# Armature_Joint_PCB_V1_1.net
KiCad netlist of a schematic drawn in EAGLE
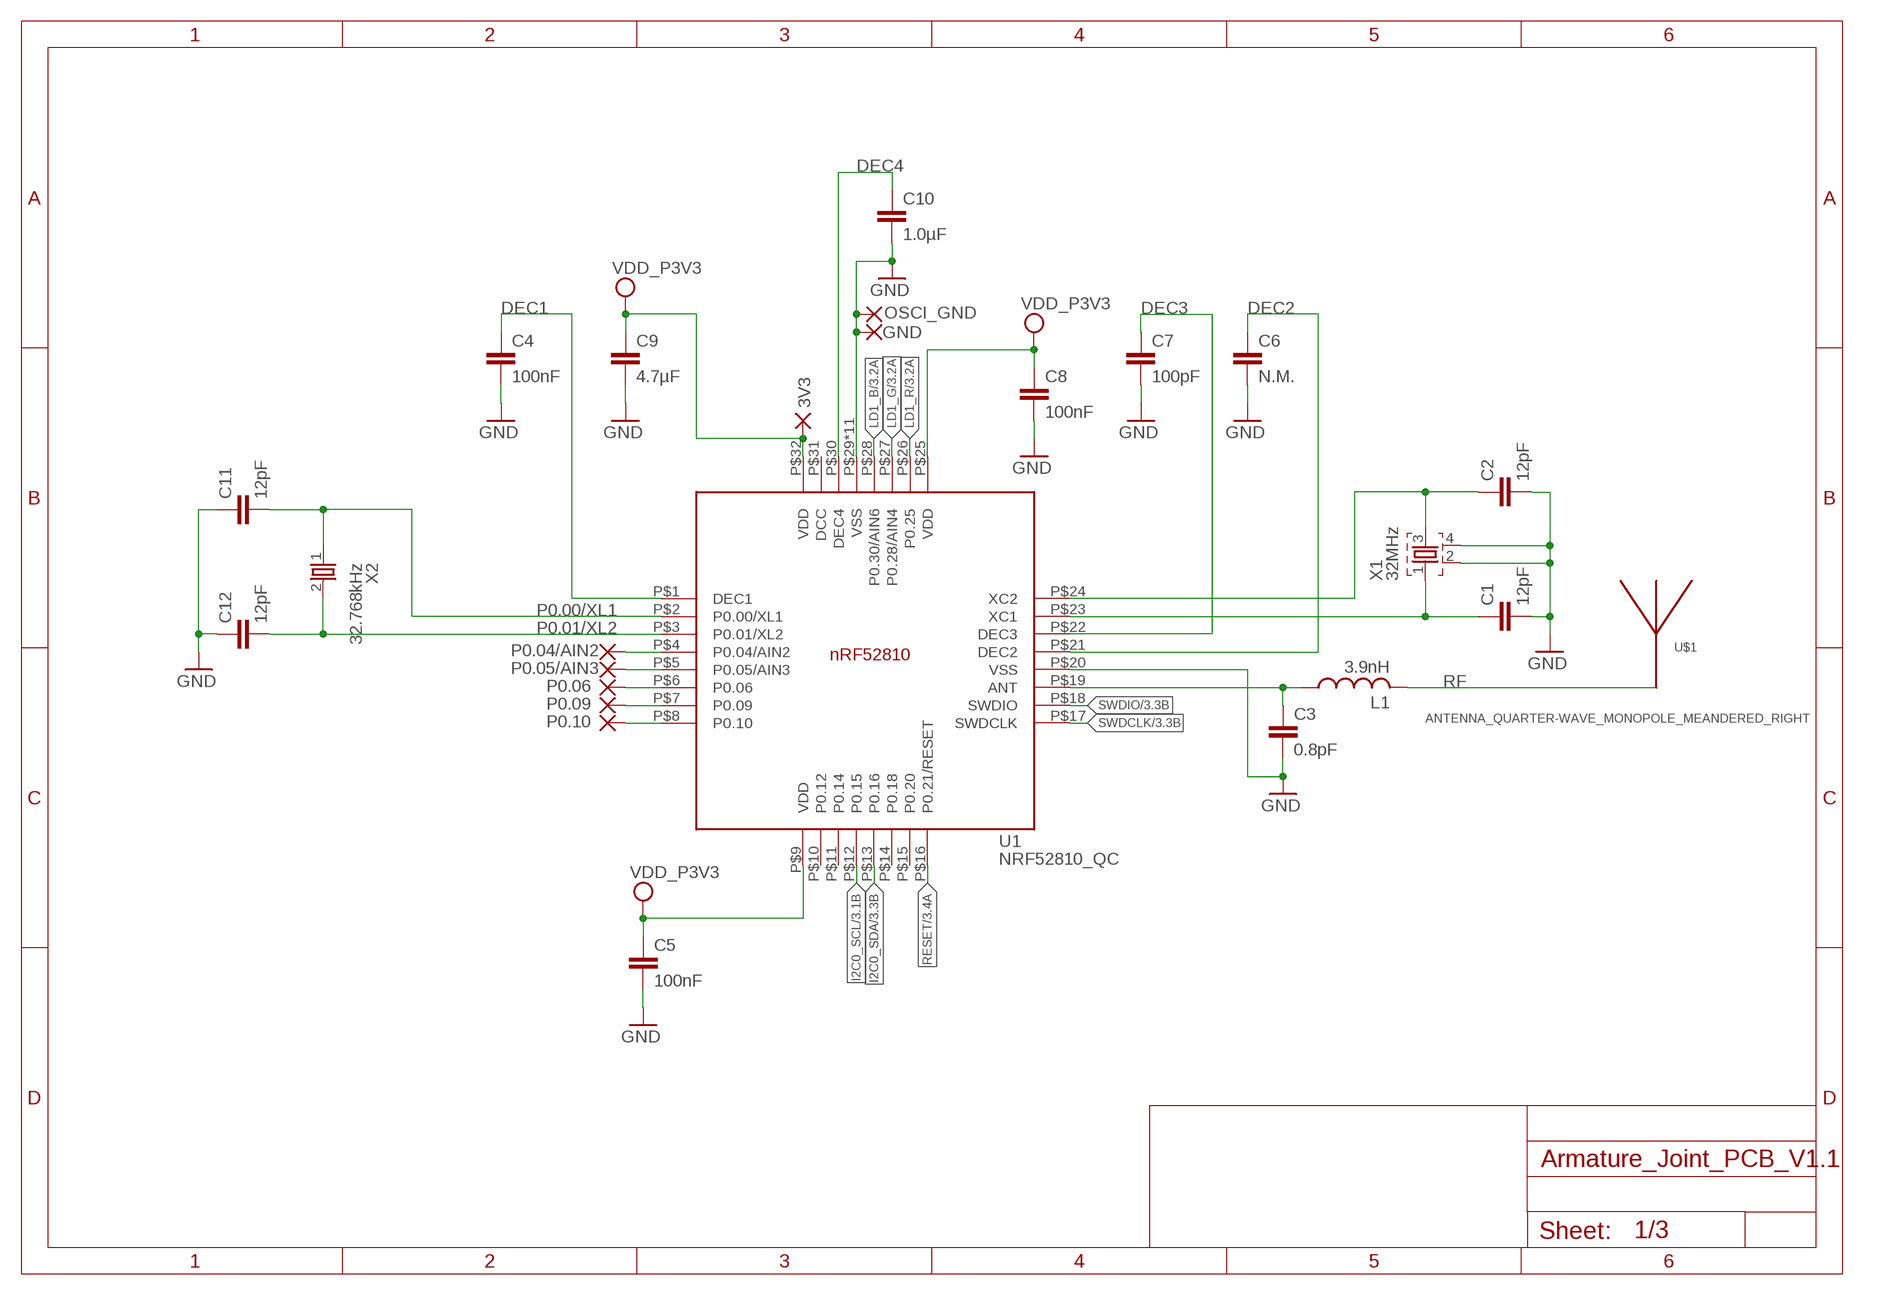
[diagram p0: schematic, sheet 1]
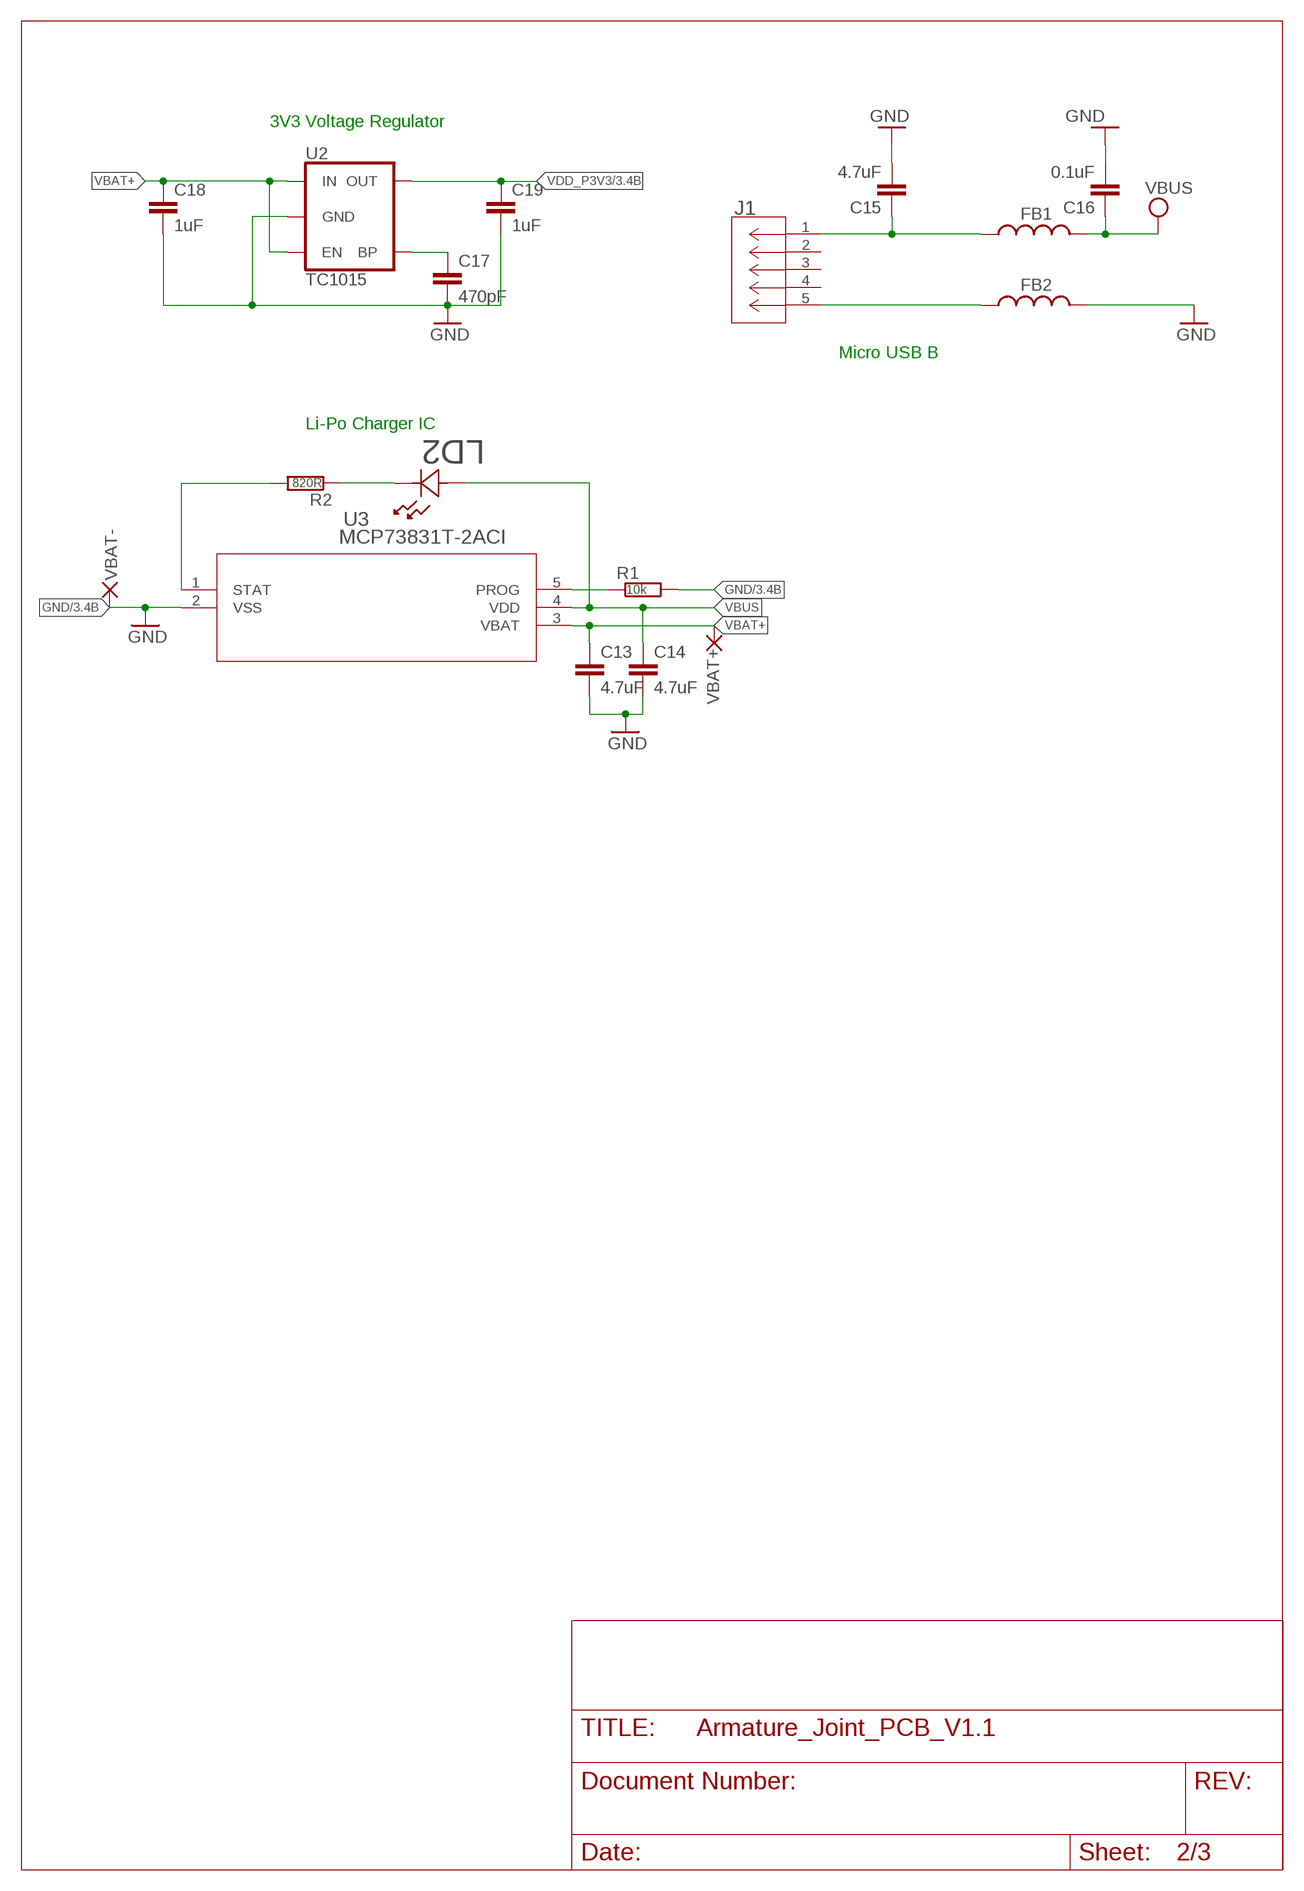
[diagram p1: schematic, sheet 2]
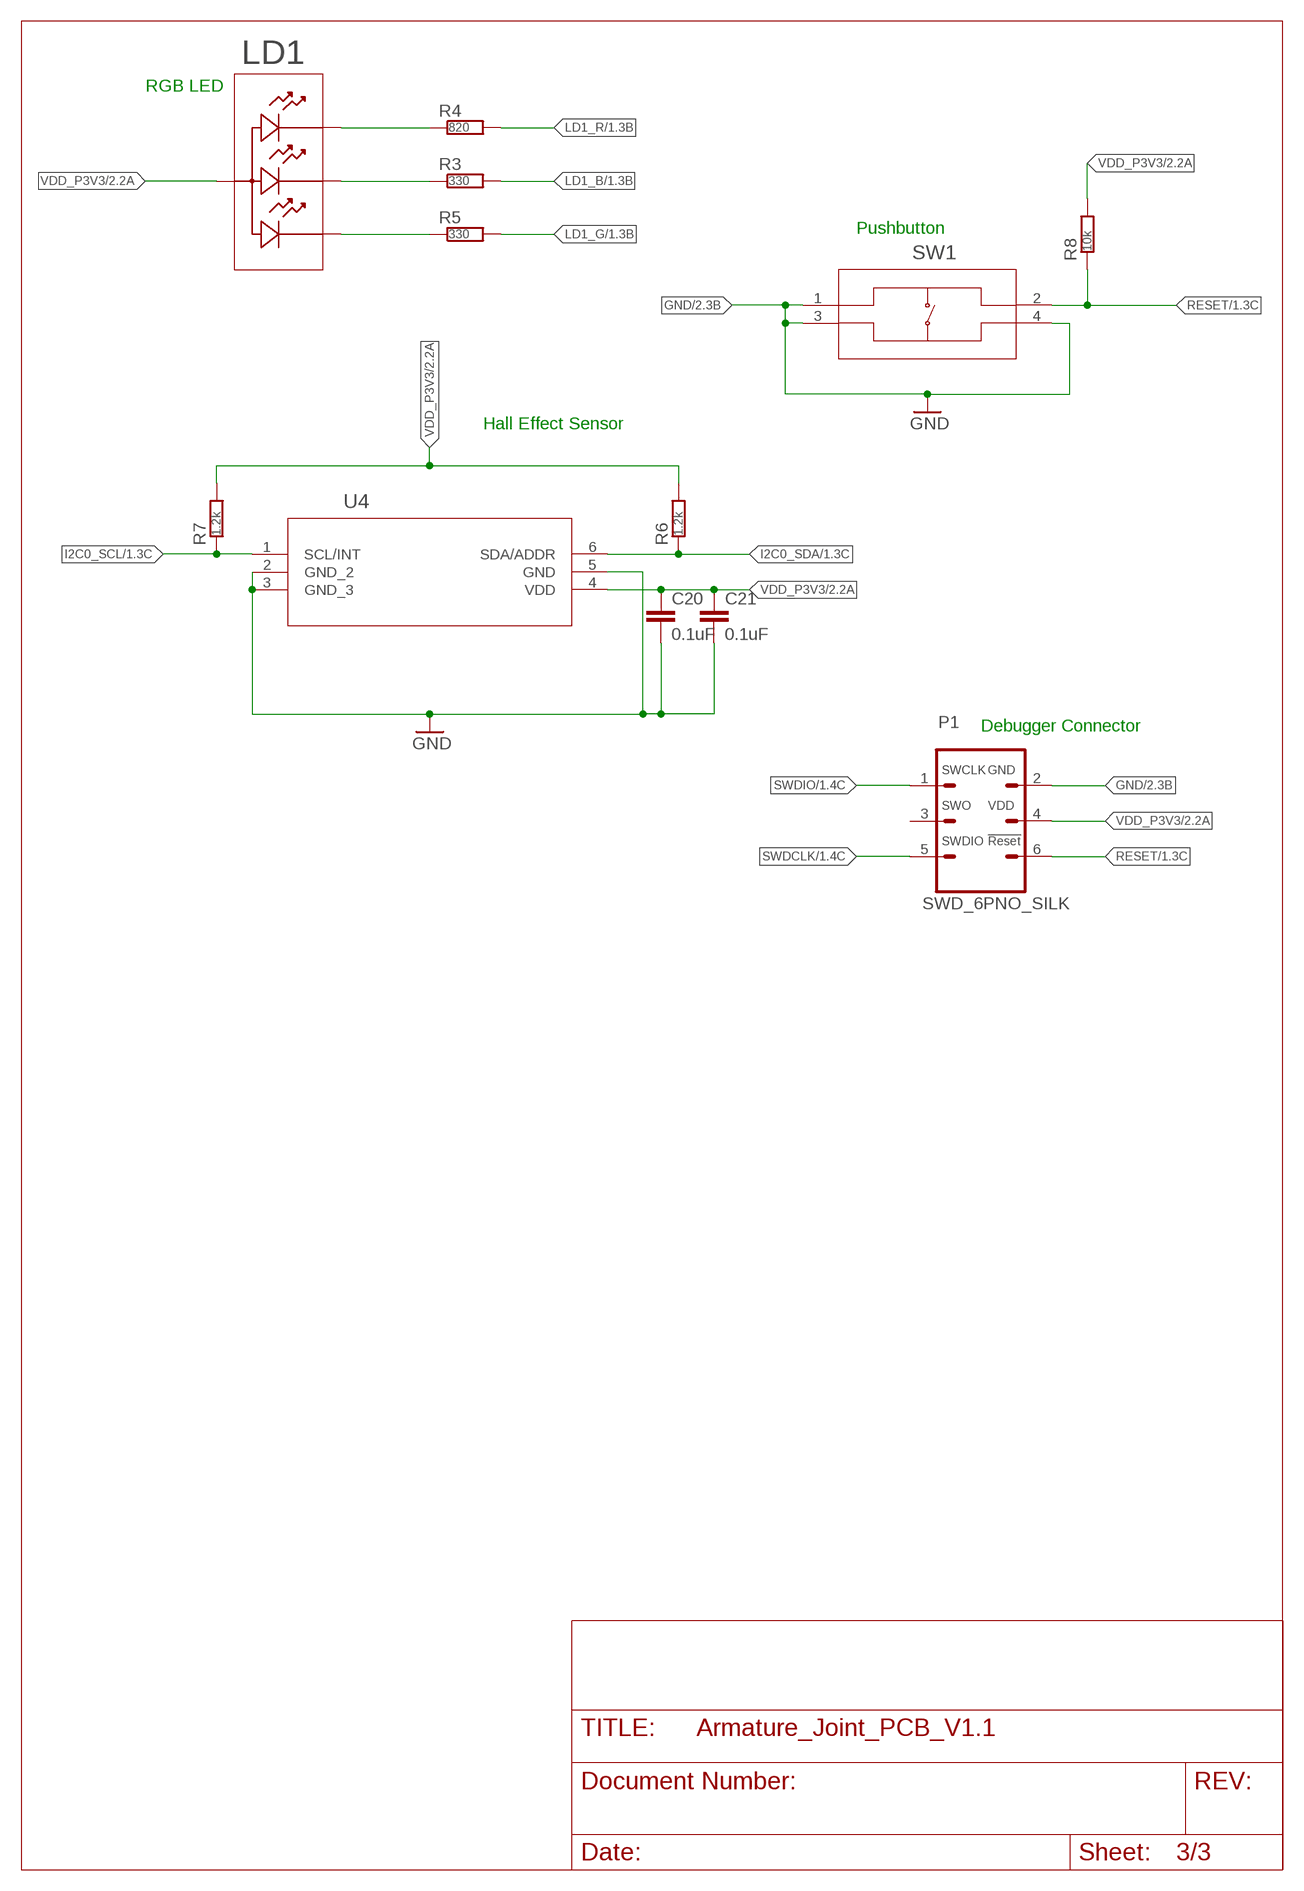
[diagram p2: schematic, sheet 3]

(export (version "E")
  (design (tool "Eeschema 10.0.6"))
  (components
    (comp (ref "C20")
      (value "0.1uF")
      (footprint "eagle-import:RESC0402_M")
      (libsource (lib "eagle-import") (part "CAPACITOR_0402_M"))
    )
    (comp (ref "C21")
      (value "0.1uF")
      (footprint "eagle-import:RESC0402_M")
      (libsource (lib "eagle-import") (part "CAPACITOR_0402_M"))
    )
    (comp (ref "LD1")
      (value "APHF1608SEEQBDZGKCAPHF1608SEEQBDZGKC_KNB-L")
      (footprint "eagle-import:APHF1608SEEQBDZGKC_KNB-L")
      (fields
        (field (name "MANUFACTURER_PART_NUMBER") "APHF1608SEEQBDZGKC")
        (field (name "COPYRIGHT") "Copyright (C) 2018 Accelerated Designs. All rights reserved")
      )
      (libsource (lib "eagle-import") (part "APHF1608SEEQBDZGKCAPHF1608SEEQBDZGKC_KNB-L"))
    )
    (comp (ref "P1")
      (value "SWD_6PNO_SILK")
      (footprint "eagle-import:SWD_6P")
      (libsource (lib "eagle-import") (part "SWD_6PNO_SILK"))
    )
    (comp (ref "R3")
      (value "330")
      (footprint "eagle-import:RESC0402_N")
      (libsource (lib "eagle-import") (part "RESISTOR_0402_N"))
    )
    (comp (ref "R4")
      (value "820")
      (footprint "eagle-import:RESC0402_N")
      (libsource (lib "eagle-import") (part "RESISTOR_0402_N"))
    )
    (comp (ref "R5")
      (value "330")
      (footprint "eagle-import:RESC0402_N")
      (libsource (lib "eagle-import") (part "RESISTOR_0402_N"))
    )
    (comp (ref "R6")
      (value "1.2k")
      (footprint "eagle-import:RESC0402_N")
      (libsource (lib "eagle-import") (part "RESISTOR_0402_N"))
    )
    (comp (ref "R7")
      (value "1.2k")
      (footprint "eagle-import:RESC0402_N")
      (libsource (lib "eagle-import") (part "RESISTOR_0402_N"))
    )
    (comp (ref "R8")
      (value "10k")
      (footprint "eagle-import:RESC0402_N")
      (libsource (lib "eagle-import") (part "RESISTOR_0402_N"))
    )
    (comp (ref "SW1")
      (value "PTS810SJG250SMTRLFS")
      (footprint "eagle-import:PTS810")
      (fields (field (name "COPYRIGHT") "Copyright (C) 2018 Accelerated Designs. All rights reserved"))
      (libsource (lib "eagle-import") (part "PTS810SJG250SMTRLFS"))
    )
    (comp (ref "U4")
      (value "TLV493DA1B6HTSA2")
      (footprint "eagle-import:PG-TSOP6-6-5_INF")
      (fields (field (name "COPYRIGHT") "Copyright (C) 2018 Accelerated Designs. All rights reserved"))
      (libsource (lib "eagle-import") (part "TLV493DA1B6HTSA2"))
    )
    (comp (ref "C13")
      (value "4.7uF")
      (footprint "eagle-import:RESC0603_N")
      (libsource (lib "eagle-import") (part "CAPACITORCAP_0603_N"))
    )
    (comp (ref "C14")
      (value "4.7uF")
      (footprint "eagle-import:RESC0603_N")
      (libsource (lib "eagle-import") (part "CAPACITORCAP_0603_N"))
    )
    (comp (ref "C15")
      (value "4.7uF")
      (footprint "eagle-import:RESC0603_N")
      (libsource (lib "eagle-import") (part "CAPACITORCAP_0603_N"))
    )
    (comp (ref "C16")
      (value "0.1uF")
      (footprint "eagle-import:RESC0603_N")
      (libsource (lib "eagle-import") (part "CAPACITORCAP_0603_N"))
    )
    (comp (ref "C17")
      (value "470pF")
      (footprint "eagle-import:RESC0402_N")
      (libsource (lib "eagle-import") (part "CAPACITOR"))
    )
    (comp (ref "C18")
      (value "1uF")
      (footprint "eagle-import:RESC0603_N")
      (libsource (lib "eagle-import") (part "CAPACITORCAP_0603_N"))
    )
    (comp (ref "C19")
      (value "1uF")
      (footprint "eagle-import:RESC0603_N")
      (libsource (lib "eagle-import") (part "CAPACITORCAP_0603_N"))
    )
    (comp (ref "FB1")
      (value "FERRITE_BEAD")
      (footprint "eagle-import:RESC0402_M")
      (libsource (lib "eagle-import") (part "FERRITE_BEAD"))
    )
    (comp (ref "FB2")
      (value "FERRITE_BEAD")
      (footprint "eagle-import:RESC0402_M")
      (libsource (lib "eagle-import") (part "FERRITE_BEAD"))
    )
    (comp (ref "J1")
      (value "10118192-0002LF")
      (footprint "eagle-import:CONN_10118192-0002LF_AMP")
      (fields (field (name "COPYRIGHT") "Copyright (C) 2018 Accelerated Designs. All rights reserved"))
      (libsource (lib "eagle-import") (part "10118192-0002LF"))
    )
    (comp (ref "LD2")
      (value "LBQH9G-N1OO-35-1")
      (footprint "eagle-import:LED_SML-LX0402SYC-TR_LUM-M")
      (libsource (lib "eagle-import") (part "LBQH9G-N1OO-35-1"))
    )
    (comp (ref "R1")
      (value "10k")
      (footprint "eagle-import:RESC0402_N")
      (libsource (lib "eagle-import") (part "RESISTOR_0402_N"))
    )
    (comp (ref "R2")
      (value "820R")
      (footprint "eagle-import:RESC0402_N")
      (libsource (lib "eagle-import") (part "RESISTOR_0402_N"))
    )
    (comp (ref "U2")
      (value "TC1015")
      (footprint "eagle-import:SOT23-5")
      (libsource (lib "eagle-import") (part "TC1015"))
    )
    (comp (ref "U3")
      (value "MCP73831T-2ACI")
      (footprint "eagle-import:SOT-23-5_MC_MCH")
      (fields (field (name "MANUFACTURER_PART_NUMBER") "MCP73831T-2ACI/OT"))
      (libsource (lib "eagle-import") (part "MCP73831T-2ACI/OT"))
    )
    (comp (ref "VBAT+")
      (value "VBAT+")
      (footprint "eagle-import:SMD1,27-2,54")
      (libsource (lib "eagle-import") (part "SMD2"))
    )
    (comp (ref "VBAT-")
      (value "GND")
      (footprint "eagle-import:SMD1,27-2,54")
      (libsource (lib "eagle-import") (part "SMD2"))
    )
    (comp (ref "3V3")
      (value "vdd_p3v3")
      (footprint "eagle-import:SMD1,27-2,54")
      (libsource (lib "eagle-import") (part "SMD2"))
    )
    (comp (ref "C1")
      (value "12pF")
      (footprint "eagle-import:RESC0402_N")
      (libsource (lib "eagle-import") (part "CAPACITOR"))
    )
    (comp (ref "C2")
      (value "12pF")
      (footprint "eagle-import:RESC0402_N")
      (libsource (lib "eagle-import") (part "CAPACITOR"))
    )
    (comp (ref "C3")
      (value "0.8pF")
      (footprint "eagle-import:RESC0402_N")
      (libsource (lib "eagle-import") (part "CAPACITOR"))
    )
    (comp (ref "C4")
      (value "100nF")
      (footprint "eagle-import:RESC0402_N")
      (libsource (lib "eagle-import") (part "CAPACITOR"))
    )
    (comp (ref "C5")
      (value "100nF")
      (footprint "eagle-import:RESC0402_N")
      (libsource (lib "eagle-import") (part "CAPACITOR"))
    )
    (comp (ref "C6")
      (value "N.M.")
      (footprint "eagle-import:RESC0402_N")
      (libsource (lib "eagle-import") (part "CAPACITOR"))
    )
    (comp (ref "C7")
      (value "100pF")
      (footprint "eagle-import:RESC0402_N")
      (libsource (lib "eagle-import") (part "CAPACITOR"))
    )
    (comp (ref "C8")
      (value "100nF")
      (footprint "eagle-import:RESC0402_N")
      (libsource (lib "eagle-import") (part "CAPACITOR"))
    )
    (comp (ref "C9")
      (value "4.7µF")
      (footprint "eagle-import:RESC0603_N")
      (libsource (lib "eagle-import") (part "CAPACITORCAP_0603_N"))
    )
    (comp (ref "C10")
      (value "1.0µF")
      (footprint "eagle-import:RESC0603_N")
      (libsource (lib "eagle-import") (part "CAPACITORCAP_0603_N"))
    )
    (comp (ref "C11")
      (value "12pF")
      (footprint "eagle-import:RESC0402_N")
      (libsource (lib "eagle-import") (part "CAPACITOR"))
    )
    (comp (ref "C12")
      (value "12pF")
      (footprint "eagle-import:RESC0402_N")
      (libsource (lib "eagle-import") (part "CAPACITOR"))
    )
    (comp (ref "GND")
      (value "GND")
      (footprint "eagle-import:SMD1,27-2,54")
      (libsource (lib "eagle-import") (part "SMD2"))
    )
    (comp (ref "L1")
      (value "3.9nH")
      (footprint "eagle-import:RESC0402_N")
      (libsource (lib "eagle-import") (part "INDUCTOR_0402_N"))
    )
    (comp (ref "OSCI_GND")
      (value "GND")
      (footprint "eagle-import:2,15_1,0")
      (libsource (lib "eagle-import") (part "2,15/1,0"))
    )
    (comp (ref "P0.04/AIN2")
      (value "P0.04/AIN2")
      (footprint "eagle-import:SMD1,27-2,54")
      (libsource (lib "eagle-import") (part "SMD2"))
    )
    (comp (ref "P0.05/AIN3")
      (value "P0.05/AIN3")
      (footprint "eagle-import:SMD1,27-2,54")
      (libsource (lib "eagle-import") (part "SMD2"))
    )
    (comp (ref "P0.06")
      (value "P0.06")
      (footprint "eagle-import:SMD1,27-2,54")
      (libsource (lib "eagle-import") (part "SMD2"))
    )
    (comp (ref "P0.09")
      (value "P0.09")
      (footprint "eagle-import:SMD1,27-2,54")
      (libsource (lib "eagle-import") (part "SMD2"))
    )
    (comp (ref "P0.10")
      (value "P0.10")
      (footprint "eagle-import:SMD1,27-2,54")
      (libsource (lib "eagle-import") (part "SMD2"))
    )
    (comp (ref "U$1")
      (value "ANTENNA_QUARTER-WAVE_MONOPOLE_MEANDERED_RIGHT")
      (footprint "eagle-import:QWMP_MEANDERED_RIGHT_+6")
      (libsource (lib "eagle-import") (part "ANTENNA_QUARTER-WAVE_MONOPOLE_MEANDERED_RIGHT"))
    )
    (comp (ref "U1")
      (value "NRF52810_QC")
      (footprint "eagle-import:QFN50P500X500X90-32_N")
      (libsource (lib "eagle-import") (part "NRF52810_QC"))
    )
    (comp (ref "X1")
      (value "32MHz")
      (footprint "eagle-import:BT-XTAL_2016_N")
      (libsource (lib "eagle-import") (part "XTAL_32MHZ"))
    )
    (comp (ref "X2")
      (value "32.768kHz")
      (footprint "eagle-import:XTAL_3215_N")
      (libsource (lib "eagle-import") (part "XTAL_32KHZ"))
    )
  )
  (nets
    (net (code "1") (name "DEC1") (class "Default")
      (node (ref "C4") (pin "1") (pinfunction "1_1") (pintype "passive"))
      (node (ref "U1") (pin "P$1") (pinfunction "DEC1_P$1") (pintype "bidirectional"))
    )
    (net (code "2") (name "DEC2") (class "Default")
      (node (ref "C6") (pin "1") (pinfunction "1_1") (pintype "passive"))
      (node (ref "U1") (pin "P$21") (pinfunction "DEC2_P$21") (pintype "bidirectional"))
    )
    (net (code "3") (name "DEC3") (class "Default")
      (node (ref "C7") (pin "1") (pinfunction "1_1") (pintype "passive"))
      (node (ref "U1") (pin "P$22") (pinfunction "DEC3_P$22") (pintype "bidirectional"))
    )
    (net (code "4") (name "DEC4") (class "Default")
      (node (ref "C10") (pin "1") (pinfunction "1_1") (pintype "passive"))
      (node (ref "U1") (pin "P$30") (pinfunction "DEC4_P$30") (pintype "bidirectional"))
    )
    (net (code "5") (name "GND") (class "Default")
      (node (ref "C1") (pin "2") (pinfunction "2_2") (pintype "passive"))
      (node (ref "C10") (pin "2") (pinfunction "2_2") (pintype "passive"))
      (node (ref "C11") (pin "1") (pinfunction "1_1") (pintype "passive"))
      (node (ref "C12") (pin "1") (pinfunction "1_1") (pintype "passive"))
      (node (ref "C13") (pin "2") (pinfunction "2_2") (pintype "passive"))
      (node (ref "C14") (pin "2") (pinfunction "2_2") (pintype "passive"))
      (node (ref "C15") (pin "2") (pinfunction "2_2") (pintype "passive"))
      (node (ref "C16") (pin "2") (pinfunction "2_2") (pintype "passive"))
      (node (ref "C17") (pin "2") (pinfunction "2_2") (pintype "passive"))
      (node (ref "C18") (pin "2") (pinfunction "2_2") (pintype "passive"))
      (node (ref "C19") (pin "2") (pinfunction "2_2") (pintype "passive"))
      (node (ref "C2") (pin "2") (pinfunction "2_2") (pintype "passive"))
      (node (ref "C20") (pin "2") (pinfunction "2_2") (pintype "passive"))
      (node (ref "C21") (pin "2") (pinfunction "2_2") (pintype "passive"))
      (node (ref "C3") (pin "2") (pinfunction "2_2") (pintype "passive"))
      (node (ref "C4") (pin "2") (pinfunction "2_2") (pintype "passive"))
      (node (ref "C5") (pin "2") (pinfunction "2_2") (pintype "passive"))
      (node (ref "C6") (pin "2") (pinfunction "2_2") (pintype "passive"))
      (node (ref "C7") (pin "2") (pinfunction "2_2") (pintype "passive"))
      (node (ref "C8") (pin "2") (pinfunction "2_2") (pintype "passive"))
      (node (ref "C9") (pin "2") (pinfunction "2_2") (pintype "passive"))
      (node (ref "FB2") (pin "2") (pinfunction "2_2") (pintype "passive"))
      (node (ref "GND") (pin "1") (pinfunction "P_1") (pintype "passive"))
      (node (ref "OSCI_GND") (pin "1") (pinfunction "P_1") (pintype "passive"))
      (node (ref "P1") (pin "2") (pinfunction "2_2") (pintype "bidirectional"))
      (node (ref "R1") (pin "2") (pinfunction "2_2") (pintype "passive"))
      (node (ref "SW1") (pin "1") (pinfunction "1_1") (pintype "passive"))
      (node (ref "SW1") (pin "3") (pinfunction "3_3") (pintype "passive"))
      (node (ref "SW1") (pin "4") (pinfunction "4_4") (pintype "passive"))
      (node (ref "U1") (pin "P$20") (pinfunction "VSS_P$20") (pintype "bidirectional"))
      (node (ref "U1") (pin "P$29") (pinfunction "VSS_P$29") (pintype "bidirectional"))
      (node (ref "U1") (pin "P$33") (pinfunction "VSS_P$33") (pintype "bidirectional"))
      (node (ref "U1") (pin "P$34") (pinfunction "VSS_P$34") (pintype "bidirectional"))
      (node (ref "U1") (pin "P$35") (pinfunction "VSS_P$35") (pintype "bidirectional"))
      (node (ref "U1") (pin "P$36") (pinfunction "VSS_P$36") (pintype "bidirectional"))
      (node (ref "U1") (pin "P$37") (pinfunction "VSS_P$37") (pintype "bidirectional"))
      (node (ref "U1") (pin "P$38") (pinfunction "VSS_P$38") (pintype "bidirectional"))
      (node (ref "U1") (pin "P$39") (pinfunction "VSS_P$39") (pintype "bidirectional"))
      (node (ref "U1") (pin "P$40") (pinfunction "VSS_P$40") (pintype "bidirectional"))
      (node (ref "U1") (pin "P$41") (pinfunction "VSS_P$41") (pintype "bidirectional"))
      (node (ref "U1") (pin "P$42") (pinfunction "VSS_P$42") (pintype "bidirectional"))
      (node (ref "U2") (pin "2") (pinfunction "GND_2") (pintype "input"))
      (node (ref "U3") (pin "2") (pinfunction "VSS_2") (pintype "passive"))
      (node (ref "U4") (pin "2") (pinfunction "GND_2_2") (pintype "passive"))
      (node (ref "U4") (pin "3") (pinfunction "GND_3_3") (pintype "passive"))
      (node (ref "U4") (pin "5") (pinfunction "GND_5") (pintype "passive"))
      (node (ref "VBAT-") (pin "1") (pinfunction "P_1") (pintype "passive"))
      (node (ref "X1") (pin "2") (pinfunction "2_2") (pintype "passive"))
      (node (ref "X1") (pin "4") (pinfunction "4_4") (pintype "passive"))
    )
    (net (code "6") (name "I2C0_SCL") (class "Default")
      (node (ref "R7") (pin "1") (pinfunction "1_1") (pintype "passive"))
      (node (ref "U1") (pin "P$12") (pinfunction "P0.15_P$12") (pintype "bidirectional"))
      (node (ref "U4") (pin "1") (pinfunction "SCL/INT_1") (pintype "input"))
    )
    (net (code "7") (name "I2C0_SDA") (class "Default")
      (node (ref "R6") (pin "1") (pinfunction "1_1") (pintype "passive"))
      (node (ref "U1") (pin "P$13") (pinfunction "P0.16_P$13") (pintype "bidirectional"))
      (node (ref "U4") (pin "6") (pinfunction "SDA/ADDR_6") (pintype "bidirectional"))
    )
    (net (code "8") (name "LD1_B") (class "Default")
      (node (ref "R3") (pin "2") (pinfunction "2_2") (pintype "passive"))
      (node (ref "U1") (pin "P$28") (pinfunction "P0.30/AIN6_P$28") (pintype "bidirectional"))
    )
    (net (code "9") (name "LD1_G") (class "Default")
      (node (ref "R5") (pin "2") (pinfunction "2_2") (pintype "passive"))
      (node (ref "U1") (pin "P$27") (pinfunction "P0.28/AIN4_P$27") (pintype "bidirectional"))
    )
    (net (code "10") (name "LD1_R") (class "Default")
      (node (ref "R4") (pin "2") (pinfunction "2_2") (pintype "passive"))
      (node (ref "U1") (pin "P$26") (pinfunction "P0.25_P$26") (pintype "bidirectional"))
    )
    (net (code "11") (name "Net-(C15-Pad1)") (class "Default")
      (node (ref "C15") (pin "1") (pinfunction "1_1") (pintype "passive"))
      (node (ref "FB1") (pin "1") (pinfunction "1_1") (pintype "passive"))
      (node (ref "J1") (pin "1") (pinfunction "1_1") (pintype "passive"))
    )
    (net (code "12") (name "Net-(FB2-Pad1)") (class "Default")
      (node (ref "FB2") (pin "1") (pinfunction "1_1") (pintype "passive"))
      (node (ref "J1") (pin "5") (pinfunction "5_5") (pintype "passive"))
    )
    (net (code "13") (name "Net-(LD1-Pad2)") (class "Default")
      (node (ref "LD1") (pin "2") (pinfunction "2_2") (pintype "passive"))
      (node (ref "R4") (pin "1") (pinfunction "1_1") (pintype "passive"))
    )
    (net (code "14") (name "Net-(LD1-Pad3)") (class "Default")
      (node (ref "LD1") (pin "3") (pinfunction "3_3") (pintype "passive"))
      (node (ref "R3") (pin "1") (pinfunction "1_1") (pintype "passive"))
    )
    (net (code "15") (name "Net-(LD1-Pad4)") (class "Default")
      (node (ref "LD1") (pin "4") (pinfunction "4_4") (pintype "passive"))
      (node (ref "R5") (pin "1") (pinfunction "1_1") (pintype "passive"))
    )
    (net (code "16") (name "Net-(LD2-Pad1)") (class "Default")
      (node (ref "LD2") (pin "1") (pinfunction "1_1") (pintype "passive"))
      (node (ref "R2") (pin "1") (pinfunction "1_1") (pintype "passive"))
    )
    (net (code "17") (name "Net-(P0.04/AIN2-P)") (class "Default")
      (node (ref "P0.04/AIN2") (pin "1") (pinfunction "P_1") (pintype "passive"))
      (node (ref "U1") (pin "P$4") (pinfunction "P0.04/AIN2_P$4") (pintype "bidirectional"))
    )
    (net (code "18") (name "Net-(P0.05/AIN3-P)") (class "Default")
      (node (ref "P0.05/AIN3") (pin "1") (pinfunction "P_1") (pintype "passive"))
      (node (ref "U1") (pin "P$5") (pinfunction "P0.05/AIN3_P$5") (pintype "bidirectional"))
    )
    (net (code "19") (name "Net-(P0.06-P)") (class "Default")
      (node (ref "P0.06") (pin "1") (pinfunction "P_1") (pintype "passive"))
      (node (ref "U1") (pin "P$6") (pinfunction "P0.06_P$6") (pintype "bidirectional"))
    )
    (net (code "20") (name "Net-(P0.09-P)") (class "Default")
      (node (ref "P0.09") (pin "1") (pinfunction "P_1") (pintype "passive"))
      (node (ref "U1") (pin "P$7") (pinfunction "P0.09_P$7") (pintype "bidirectional"))
    )
    (net (code "21") (name "Net-(P0.10-P)") (class "Default")
      (node (ref "P0.10") (pin "1") (pinfunction "P_1") (pintype "passive"))
      (node (ref "U1") (pin "P$8") (pinfunction "P0.10_P$8") (pintype "bidirectional"))
    )
    (net (code "22") (name "Net-(U1-ANT)") (class "Default")
      (node (ref "C3") (pin "1") (pinfunction "1_1") (pintype "passive"))
      (node (ref "L1") (pin "1") (pinfunction "1_1") (pintype "passive"))
      (node (ref "U1") (pin "P$19") (pinfunction "ANT_P$19") (pintype "bidirectional"))
    )
    (net (code "23") (name "Net-(U1-XC1)") (class "Default")
      (node (ref "C1") (pin "1") (pinfunction "1_1") (pintype "passive"))
      (node (ref "U1") (pin "P$23") (pinfunction "XC1_P$23") (pintype "bidirectional"))
      (node (ref "X1") (pin "1") (pinfunction "1_1") (pintype "passive"))
    )
    (net (code "24") (name "Net-(U1-XC2)") (class "Default")
      (node (ref "C2") (pin "1") (pinfunction "1_1") (pintype "passive"))
      (node (ref "U1") (pin "P$24") (pinfunction "XC2_P$24") (pintype "bidirectional"))
      (node (ref "X1") (pin "3") (pinfunction "3_3") (pintype "passive"))
    )
    (net (code "25") (name "Net-(U2-BP)") (class "Default")
      (node (ref "C17") (pin "1") (pinfunction "1_1") (pintype "passive"))
      (node (ref "U2") (pin "4") (pinfunction "BP_4") (pintype "input"))
    )
    (net (code "26") (name "Net-(U3-PROG)") (class "Default")
      (node (ref "R1") (pin "1") (pinfunction "1_1") (pintype "passive"))
      (node (ref "U3") (pin "5") (pinfunction "PROG_5") (pintype "passive"))
    )
    (net (code "27") (name "Net-(U3-STAT)") (class "Default")
      (node (ref "R2") (pin "2") (pinfunction "2_2") (pintype "passive"))
      (node (ref "U3") (pin "1") (pinfunction "STAT_1") (pintype "passive"))
    )
    (net (code "28") (name "P0.00{slash}XL1") (class "Default")
      (node (ref "C11") (pin "2") (pinfunction "2_2") (pintype "passive"))
      (node (ref "U1") (pin "P$2") (pinfunction "P0.00/XL1_P$2") (pintype "bidirectional"))
      (node (ref "X2") (pin "1") (pinfunction "1_1") (pintype "passive"))
    )
    (net (code "29") (name "P0.01{slash}XL2") (class "Default")
      (node (ref "C12") (pin "2") (pinfunction "2_2") (pintype "passive"))
      (node (ref "U1") (pin "P$3") (pinfunction "P0.01/XL2_P$3") (pintype "bidirectional"))
      (node (ref "X2") (pin "2") (pinfunction "2_2") (pintype "passive"))
    )
    (net (code "30") (name "RESET") (class "Default")
      (node (ref "P1") (pin "6") (pinfunction "6_6") (pintype "bidirectional"))
      (node (ref "R8") (pin "1") (pinfunction "1_1") (pintype "passive"))
      (node (ref "SW1") (pin "2") (pinfunction "2_2") (pintype "passive"))
      (node (ref "U1") (pin "P$16") (pinfunction "P0.21/RESET_P$16") (pintype "bidirectional"))
    )
    (net (code "31") (name "RF") (class "Default")
      (node (ref "L1") (pin "2") (pinfunction "2_2") (pintype "passive"))
      (node (ref "U$1") (pin "P$1") (pinfunction "P$1_P$1") (pintype "bidirectional"))
    )
    (net (code "32") (name "SWDCLK") (class "Default")
      (node (ref "P1") (pin "5") (pinfunction "5_5") (pintype "bidirectional"))
      (node (ref "U1") (pin "P$17") (pinfunction "SWDCLK_P$17") (pintype "bidirectional"))
    )
    (net (code "33") (name "SWDIO") (class "Default")
      (node (ref "P1") (pin "1") (pinfunction "1_1") (pintype "bidirectional"))
      (node (ref "U1") (pin "P$18") (pinfunction "SWDIO_P$18") (pintype "bidirectional"))
    )
    (net (code "34") (name "VBAT+") (class "Default")
      (node (ref "C13") (pin "1") (pinfunction "1_1") (pintype "passive"))
      (node (ref "C18") (pin "1") (pinfunction "1_1") (pintype "passive"))
      (node (ref "U2") (pin "1") (pinfunction "IN_1") (pintype "input"))
      (node (ref "U2") (pin "3") (pinfunction "EN_3") (pintype "input"))
      (node (ref "U3") (pin "3") (pinfunction "VBAT_3") (pintype "passive"))
      (node (ref "VBAT+") (pin "1") (pinfunction "P_1") (pintype "passive"))
    )
    (net (code "35") (name "VBUS") (class "Default")
      (node (ref "C14") (pin "1") (pinfunction "1_1") (pintype "passive"))
      (node (ref "C16") (pin "1") (pinfunction "1_1") (pintype "passive"))
      (node (ref "FB1") (pin "2") (pinfunction "2_2") (pintype "passive"))
      (node (ref "LD2") (pin "2") (pinfunction "2_2") (pintype "passive"))
      (node (ref "U3") (pin "4") (pinfunction "VDD_4") (pintype "passive"))
    )
    (net (code "36") (name "VDD_P3V3") (class "Default")
      (node (ref "3V3") (pin "1") (pinfunction "P_1") (pintype "passive"))
      (node (ref "C19") (pin "1") (pinfunction "1_1") (pintype "passive"))
      (node (ref "C20") (pin "1") (pinfunction "1_1") (pintype "passive"))
      (node (ref "C21") (pin "1") (pinfunction "1_1") (pintype "passive"))
      (node (ref "C5") (pin "1") (pinfunction "1_1") (pintype "passive"))
      (node (ref "C8") (pin "1") (pinfunction "1_1") (pintype "passive"))
      (node (ref "C9") (pin "1") (pinfunction "1_1") (pintype "passive"))
      (node (ref "LD1") (pin "1") (pinfunction "1_1") (pintype "passive"))
      (node (ref "P1") (pin "4") (pinfunction "4_4") (pintype "bidirectional"))
      (node (ref "R6") (pin "2") (pinfunction "2_2") (pintype "passive"))
      (node (ref "R7") (pin "2") (pinfunction "2_2") (pintype "passive"))
      (node (ref "R8") (pin "2") (pinfunction "2_2") (pintype "passive"))
      (node (ref "U1") (pin "P$25") (pinfunction "VDD_P$25") (pintype "bidirectional"))
      (node (ref "U1") (pin "P$32") (pinfunction "VDD_P$32") (pintype "bidirectional"))
      (node (ref "U1") (pin "P$9") (pinfunction "VDD_P$9") (pintype "bidirectional"))
      (node (ref "U2") (pin "5") (pinfunction "OUT_5") (pintype "passive"))
      (node (ref "U4") (pin "4") (pinfunction "VDD_4") (pintype "power_in"))
    )
    (net (code "37") (name "unconnected-(J1-Pad2)") (class "Default")
      (node (ref "J1") (pin "2") (pinfunction "2_2") (pintype "passive"))
    )
    (net (code "38") (name "unconnected-(J1-Pad3)") (class "Default")
      (node (ref "J1") (pin "3") (pinfunction "3_3") (pintype "passive"))
    )
    (net (code "39") (name "unconnected-(J1-Pad4)") (class "Default")
      (node (ref "J1") (pin "4") (pinfunction "4_4") (pintype "passive"))
    )
    (net (code "40") (name "unconnected-(P1-Pad3)") (class "Default")
      (node (ref "P1") (pin "3") (pinfunction "3_3") (pintype "no_connect"))
    )
    (net (code "41") (name "unconnected-(U1-DCC-PadP$31)") (class "Default")
      (node (ref "U1") (pin "P$31") (pinfunction "DCC_P$31") (pintype "bidirectional"))
    )
    (net (code "42") (name "unconnected-(U1-P0.12-PadP$10)") (class "Default")
      (node (ref "U1") (pin "P$10") (pinfunction "P0.12_P$10") (pintype "bidirectional"))
    )
    (net (code "43") (name "unconnected-(U1-P0.14-PadP$11)") (class "Default")
      (node (ref "U1") (pin "P$11") (pinfunction "P0.14_P$11") (pintype "bidirectional"))
    )
    (net (code "44") (name "unconnected-(U1-P0.18-PadP$14)") (class "Default")
      (node (ref "U1") (pin "P$14") (pinfunction "P0.18_P$14") (pintype "bidirectional"))
    )
    (net (code "45") (name "unconnected-(U1-P0.20-PadP$15)") (class "Default")
      (node (ref "U1") (pin "P$15") (pinfunction "P0.20_P$15") (pintype "bidirectional"))
    )
  )
)
